# 3OR_1.net
KiCad netlist of a schematic drawn in EAGLE
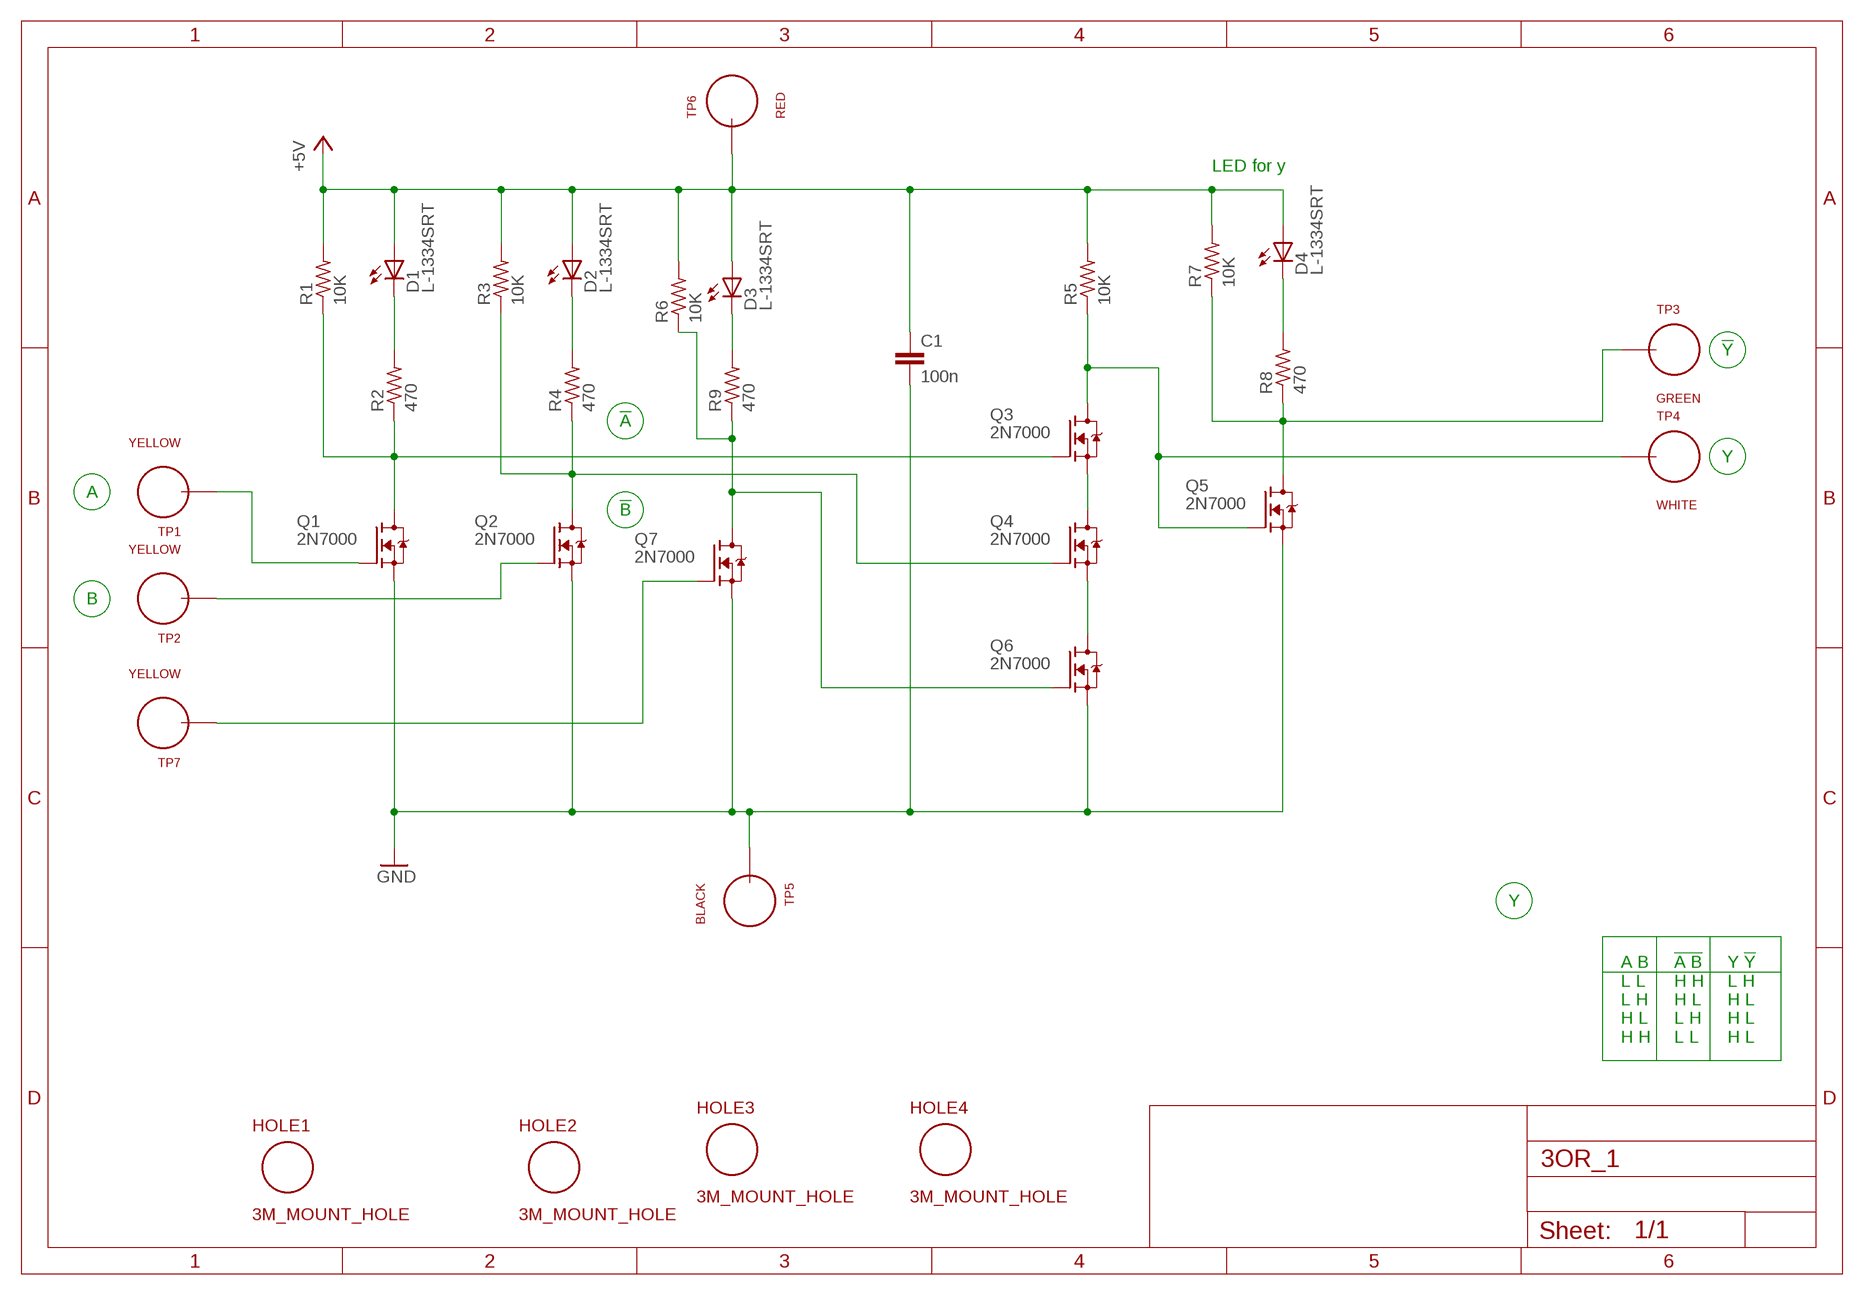
[diagram p0: schematic, sheet 1]

(export (version "E")
  (design (tool "Eeschema 10.0.6"))
  (components
    (comp (ref "C1")
      (value "100n")
      (footprint "eagle-import:CAP_P2INCH")
      (libsource (lib "eagle-import") (part "C_P2INCH"))
    )
    (comp (ref "D1")
      (value "L-1334SRT")
      (footprint "eagle-import:LED3MM")
      (libsource (lib "eagle-import") (part "L-1334SRT"))
    )
    (comp (ref "D2")
      (value "L-1334SRT")
      (footprint "eagle-import:LED3MM")
      (libsource (lib "eagle-import") (part "L-1334SRT"))
    )
    (comp (ref "D3")
      (value "L-1334SRT")
      (footprint "eagle-import:LED3MM")
      (libsource (lib "eagle-import") (part "L-1334SRT"))
    )
    (comp (ref "D4")
      (value "L-1334SRT")
      (footprint "eagle-import:LED3MM")
      (libsource (lib "eagle-import") (part "L-1334SRT"))
    )
    (comp (ref "HOLE1")
      (value "3M_MOUNT_HOLE")
      (footprint "eagle-import:3M_HOLE")
      (libsource (lib "eagle-import") (part "3M_MOUNT_HOLE"))
    )
    (comp (ref "HOLE2")
      (value "3M_MOUNT_HOLE")
      (footprint "eagle-import:3M_HOLE")
      (libsource (lib "eagle-import") (part "3M_MOUNT_HOLE"))
    )
    (comp (ref "HOLE3")
      (value "3M_MOUNT_HOLE")
      (footprint "eagle-import:3M_HOLE")
      (libsource (lib "eagle-import") (part "3M_MOUNT_HOLE"))
    )
    (comp (ref "HOLE4")
      (value "3M_MOUNT_HOLE")
      (footprint "eagle-import:3M_HOLE")
      (libsource (lib "eagle-import") (part "3M_MOUNT_HOLE"))
    )
    (comp (ref "Q1")
      (value "2N7000")
      (footprint "eagle-import:TO92-DGS")
      (libsource (lib "eagle-import") (part "2N7000"))
    )
    (comp (ref "Q2")
      (value "2N7000")
      (footprint "eagle-import:TO92-DGS")
      (libsource (lib "eagle-import") (part "2N7000"))
    )
    (comp (ref "Q3")
      (value "2N7000")
      (footprint "eagle-import:TO92-DGS")
      (libsource (lib "eagle-import") (part "2N7000"))
    )
    (comp (ref "Q4")
      (value "2N7000")
      (footprint "eagle-import:TO92-DGS")
      (libsource (lib "eagle-import") (part "2N7000"))
    )
    (comp (ref "Q5")
      (value "2N7000")
      (footprint "eagle-import:TO92-DGS")
      (libsource (lib "eagle-import") (part "2N7000"))
    )
    (comp (ref "Q6")
      (value "2N7000")
      (footprint "eagle-import:TO92-DGS")
      (libsource (lib "eagle-import") (part "2N7000"))
    )
    (comp (ref "Q7")
      (value "2N7000")
      (footprint "eagle-import:TO92-DGS")
      (libsource (lib "eagle-import") (part "2N7000"))
    )
    (comp (ref "R1")
      (value "10K")
      (footprint "eagle-import:R_P2INCH")
      (libsource (lib "eagle-import") (part "R_P2INCH"))
    )
    (comp (ref "R2")
      (value "470")
      (footprint "eagle-import:R_P2INCH")
      (libsource (lib "eagle-import") (part "R_P2INCH"))
    )
    (comp (ref "R3")
      (value "10K")
      (footprint "eagle-import:R_P2INCH")
      (libsource (lib "eagle-import") (part "R_P2INCH"))
    )
    (comp (ref "R4")
      (value "470")
      (footprint "eagle-import:R_P2INCH")
      (libsource (lib "eagle-import") (part "R_P2INCH"))
    )
    (comp (ref "R5")
      (value "10K")
      (footprint "eagle-import:R_P2INCH")
      (libsource (lib "eagle-import") (part "R_P2INCH"))
    )
    (comp (ref "R6")
      (value "10K")
      (footprint "eagle-import:R_P2INCH")
      (libsource (lib "eagle-import") (part "R_P2INCH"))
    )
    (comp (ref "R7")
      (value "10K")
      (footprint "eagle-import:R_P2INCH")
      (libsource (lib "eagle-import") (part "R_P2INCH"))
    )
    (comp (ref "R8")
      (value "470")
      (footprint "eagle-import:R_P2INCH")
      (libsource (lib "eagle-import") (part "R_P2INCH"))
    )
    (comp (ref "R9")
      (value "470")
      (footprint "eagle-import:R_P2INCH")
      (libsource (lib "eagle-import") (part "R_P2INCH"))
    )
    (comp (ref "TP1")
      (value "YELLOW")
      (footprint "eagle-import:TEST_LOOP")
      (libsource (lib "eagle-import") (part "TEST_LOOP"))
    )
    (comp (ref "TP2")
      (value "YELLOW")
      (footprint "eagle-import:TEST_LOOP")
      (libsource (lib "eagle-import") (part "TEST_LOOP"))
    )
    (comp (ref "TP3")
      (value "GREEN")
      (footprint "eagle-import:TEST_LOOP")
      (libsource (lib "eagle-import") (part "TEST_LOOP"))
    )
    (comp (ref "TP4")
      (value "WHITE")
      (footprint "eagle-import:TEST_LOOP")
      (libsource (lib "eagle-import") (part "TEST_LOOP"))
    )
    (comp (ref "TP5")
      (value "BLACK")
      (footprint "eagle-import:TEST_LOOP")
      (libsource (lib "eagle-import") (part "TEST_LOOP"))
    )
    (comp (ref "TP6")
      (value "RED")
      (footprint "eagle-import:TEST_LOOP")
      (libsource (lib "eagle-import") (part "TEST_LOOP"))
    )
    (comp (ref "TP7")
      (value "YELLOW")
      (footprint "eagle-import:TEST_LOOP")
      (libsource (lib "eagle-import") (part "TEST_LOOP"))
    )
  )
  (nets
    (net (code "1") (name "+5V") (class "Default")
      (node (ref "C1") (pin "1") (pinfunction "1_1") (pintype "passive"))
      (node (ref "D1") (pin "A") (pinfunction "A_A") (pintype "passive"))
      (node (ref "D2") (pin "A") (pinfunction "A_A") (pintype "passive"))
      (node (ref "D3") (pin "A") (pinfunction "A_A") (pintype "passive"))
      (node (ref "D4") (pin "A") (pinfunction "A_A") (pintype "passive"))
      (node (ref "R1") (pin "2") (pinfunction "2_2") (pintype "passive"))
      (node (ref "R3") (pin "2") (pinfunction "2_2") (pintype "passive"))
      (node (ref "R5") (pin "2") (pinfunction "2_2") (pintype "passive"))
      (node (ref "R6") (pin "2") (pinfunction "2_2") (pintype "passive"))
      (node (ref "R7") (pin "2") (pinfunction "2_2") (pintype "passive"))
      (node (ref "TP6") (pin "P$1") (pinfunction "P$1_P$1") (pintype "bidirectional"))
    )
    (net (code "2") (name "GND") (class "Default")
      (node (ref "C1") (pin "2") (pinfunction "2_2") (pintype "passive"))
      (node (ref "Q1") (pin "S") (pinfunction "S_S") (pintype "passive"))
      (node (ref "Q2") (pin "S") (pinfunction "S_S") (pintype "passive"))
      (node (ref "Q5") (pin "S") (pinfunction "S_S") (pintype "passive"))
      (node (ref "Q6") (pin "S") (pinfunction "S_S") (pintype "passive"))
      (node (ref "Q7") (pin "S") (pinfunction "S_S") (pintype "passive"))
      (node (ref "TP5") (pin "P$1") (pinfunction "P$1_P$1") (pintype "bidirectional"))
    )
    (net (code "3") (name "Net-(D1-C)") (class "Default")
      (node (ref "D1") (pin "K") (pinfunction "C_K") (pintype "passive"))
      (node (ref "R2") (pin "2") (pinfunction "2_2") (pintype "passive"))
    )
    (net (code "4") (name "Net-(D2-C)") (class "Default")
      (node (ref "D2") (pin "K") (pinfunction "C_K") (pintype "passive"))
      (node (ref "R4") (pin "2") (pinfunction "2_2") (pintype "passive"))
    )
    (net (code "5") (name "Net-(D3-C)") (class "Default")
      (node (ref "D3") (pin "K") (pinfunction "C_K") (pintype "passive"))
      (node (ref "R9") (pin "2") (pinfunction "2_2") (pintype "passive"))
    )
    (net (code "6") (name "Net-(D4-C)") (class "Default")
      (node (ref "D4") (pin "K") (pinfunction "C_K") (pintype "passive"))
      (node (ref "R8") (pin "2") (pinfunction "2_2") (pintype "passive"))
    )
    (net (code "7") (name "Net-(Q1-PadD)") (class "Default")
      (node (ref "Q1") (pin "D") (pinfunction "D_D") (pintype "passive"))
      (node (ref "Q3") (pin "G") (pinfunction "G_G") (pintype "passive"))
      (node (ref "R1") (pin "1") (pinfunction "1_1") (pintype "passive"))
      (node (ref "R2") (pin "1") (pinfunction "1_1") (pintype "passive"))
    )
    (net (code "8") (name "Net-(Q1-PadG)") (class "Default")
      (node (ref "Q1") (pin "G") (pinfunction "G_G") (pintype "passive"))
      (node (ref "TP1") (pin "P$1") (pinfunction "P$1_P$1") (pintype "bidirectional"))
    )
    (net (code "9") (name "Net-(Q2-PadD)") (class "Default")
      (node (ref "Q2") (pin "D") (pinfunction "D_D") (pintype "passive"))
      (node (ref "Q4") (pin "G") (pinfunction "G_G") (pintype "passive"))
      (node (ref "R3") (pin "1") (pinfunction "1_1") (pintype "passive"))
      (node (ref "R4") (pin "1") (pinfunction "1_1") (pintype "passive"))
    )
    (net (code "10") (name "Net-(Q2-PadG)") (class "Default")
      (node (ref "Q2") (pin "G") (pinfunction "G_G") (pintype "passive"))
      (node (ref "TP2") (pin "P$1") (pinfunction "P$1_P$1") (pintype "bidirectional"))
    )
    (net (code "11") (name "Net-(Q3-PadD)") (class "Default")
      (node (ref "Q3") (pin "D") (pinfunction "D_D") (pintype "passive"))
      (node (ref "Q5") (pin "G") (pinfunction "G_G") (pintype "passive"))
      (node (ref "R5") (pin "1") (pinfunction "1_1") (pintype "passive"))
      (node (ref "TP4") (pin "P$1") (pinfunction "P$1_P$1") (pintype "bidirectional"))
    )
    (net (code "12") (name "Net-(Q3-PadS)") (class "Default")
      (node (ref "Q3") (pin "S") (pinfunction "S_S") (pintype "passive"))
      (node (ref "Q4") (pin "D") (pinfunction "D_D") (pintype "passive"))
    )
    (net (code "13") (name "Net-(Q4-PadS)") (class "Default")
      (node (ref "Q4") (pin "S") (pinfunction "S_S") (pintype "passive"))
      (node (ref "Q6") (pin "D") (pinfunction "D_D") (pintype "passive"))
    )
    (net (code "14") (name "Net-(Q5-PadD)") (class "Default")
      (node (ref "Q5") (pin "D") (pinfunction "D_D") (pintype "passive"))
      (node (ref "R7") (pin "1") (pinfunction "1_1") (pintype "passive"))
      (node (ref "R8") (pin "1") (pinfunction "1_1") (pintype "passive"))
      (node (ref "TP3") (pin "P$1") (pinfunction "P$1_P$1") (pintype "bidirectional"))
    )
    (net (code "15") (name "Net-(Q6-PadG)") (class "Default")
      (node (ref "Q6") (pin "G") (pinfunction "G_G") (pintype "passive"))
      (node (ref "Q7") (pin "D") (pinfunction "D_D") (pintype "passive"))
      (node (ref "R6") (pin "1") (pinfunction "1_1") (pintype "passive"))
      (node (ref "R9") (pin "1") (pinfunction "1_1") (pintype "passive"))
    )
    (net (code "16") (name "Net-(Q7-PadG)") (class "Default")
      (node (ref "Q7") (pin "G") (pinfunction "G_G") (pintype "passive"))
      (node (ref "TP7") (pin "P$1") (pinfunction "P$1_P$1") (pintype "bidirectional"))
    )
  )
)
